# aurora-halo.net
KiCad netlist of a schematic drawn in EAGLE
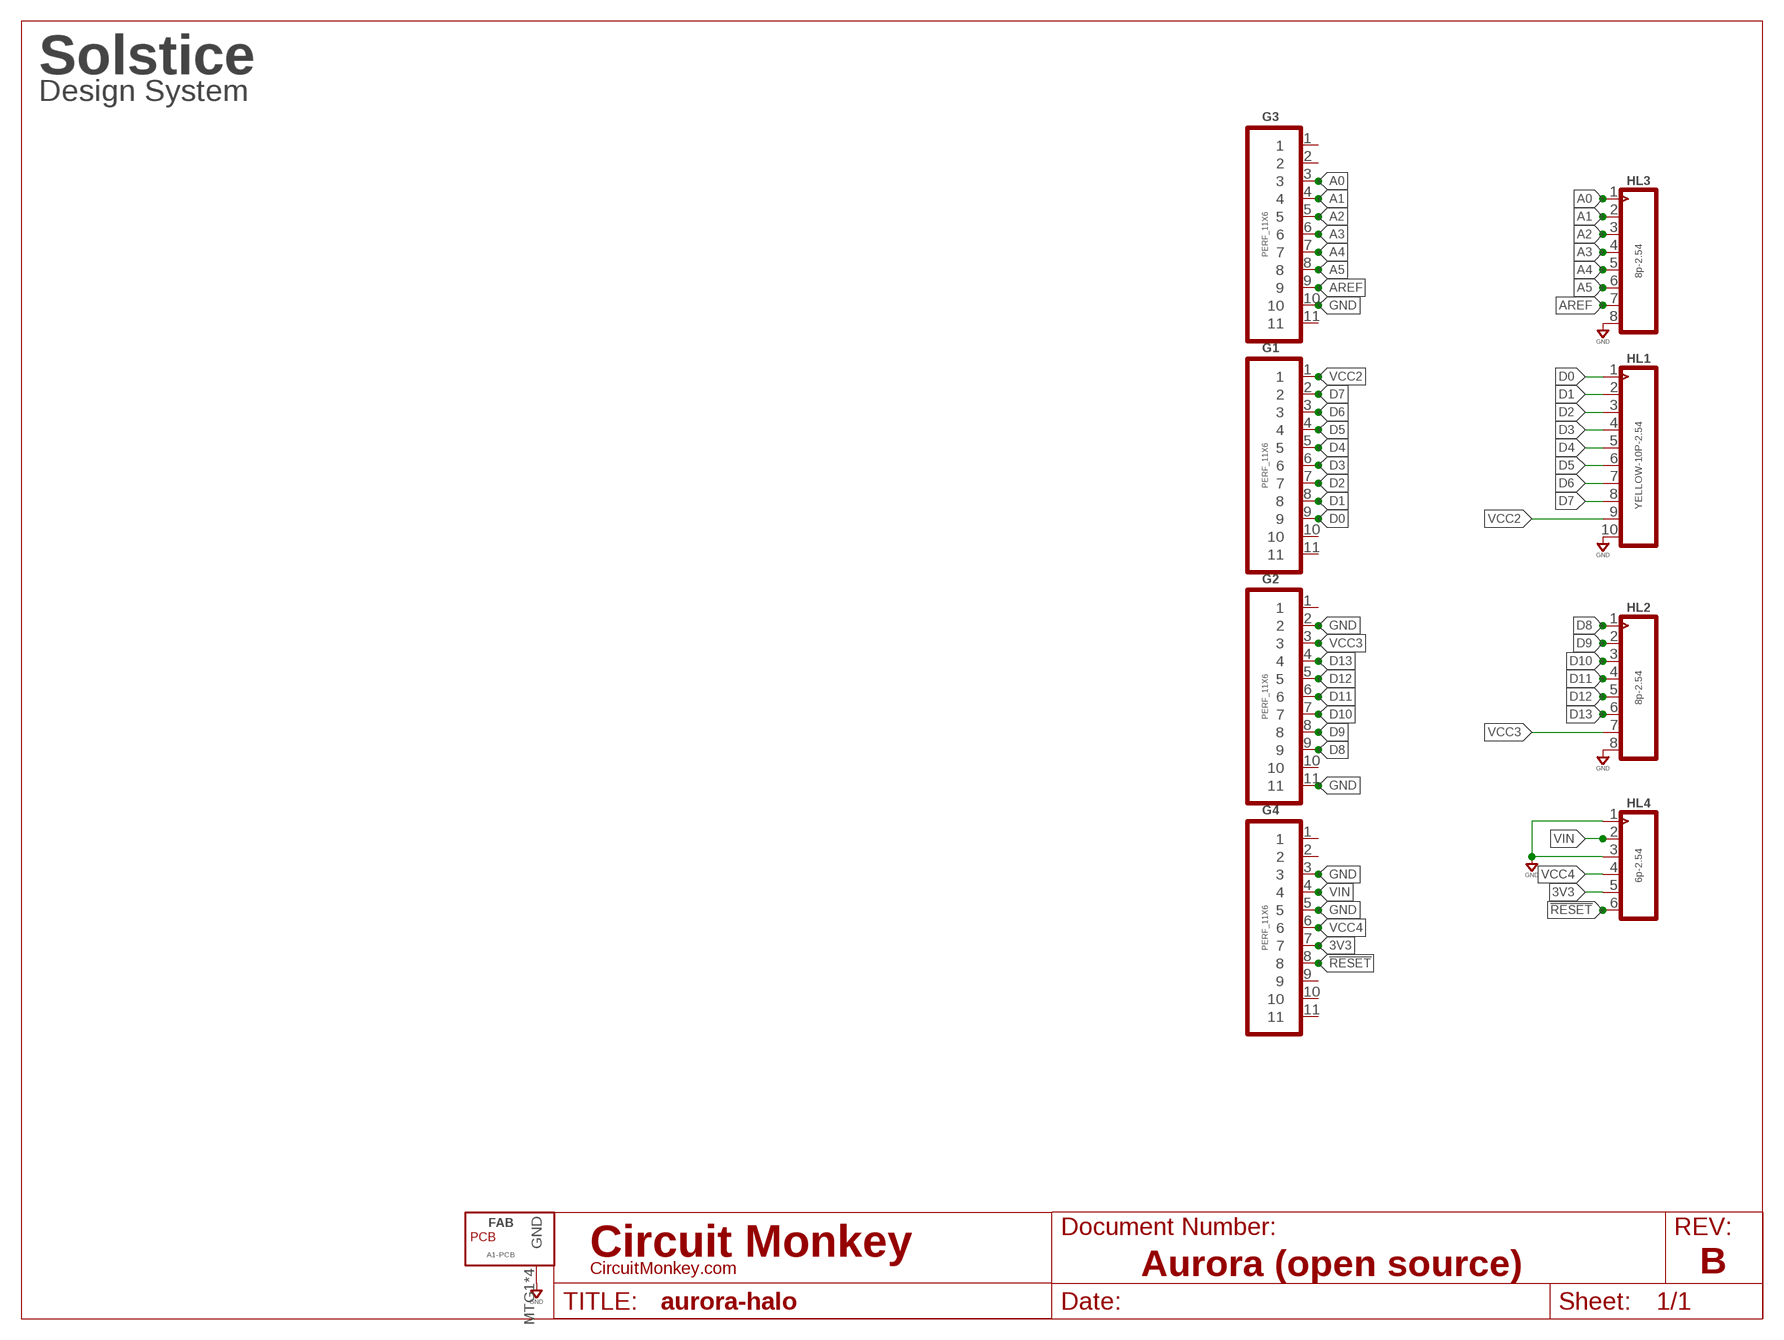
[diagram p0: schematic, sheet 1]

(export (version "E")
  (design (tool "Eeschema 10.0.6"))
  (components
    (comp (ref "FAB")
      (value "A1-PCB")
      (footprint "eagle-import:PCB-HALO-A1")
      (libsource (lib "eagle-import") (part "PCB-4-MTG-HALO-A1"))
    )
    (comp (ref "G1")
      (value "PERF_11X6")
      (footprint "eagle-import:PERF_6X11")
      (libsource (lib "eagle-import") (part "PERF_11X?6"))
    )
    (comp (ref "G2")
      (value "PERF_11X6")
      (footprint "eagle-import:PERF_6X11")
      (libsource (lib "eagle-import") (part "PERF_11X?6"))
    )
    (comp (ref "G3")
      (value "PERF_11X6")
      (footprint "eagle-import:PERF_6X11")
      (libsource (lib "eagle-import") (part "PERF_11X?6"))
    )
    (comp (ref "G4")
      (value "PERF_11X6")
      (footprint "eagle-import:PERF_6X11")
      (libsource (lib "eagle-import") (part "PERF_11X?6"))
    )
    (comp (ref "HL1")
      (value "YELLOW-10P-2.54")
      (footprint "eagle-import:H10-2.54")
      (fields (field (name "MPN") "F185-1110A1BSYC1"))
      (libsource (lib "eagle-import") (part "DIP-YELLOW-FEMALE-HEADER-VERT(10P-2.54)"))
    )
    (comp (ref "HL2")
      (value "8p-2.54")
      (footprint "eagle-import:H8-2.54")
      (fields (field (name "MPN") "F185-1108A1BSYC1"))
      (libsource (lib "eagle-import") (part "DIP-BLACK-FEMALE-HEADER-VERT(8P-2.54)"))
    )
    (comp (ref "HL3")
      (value "8p-2.54")
      (footprint "eagle-import:H8-2.54")
      (fields (field (name "MPN") "F185-1108A1BSYC1"))
      (libsource (lib "eagle-import") (part "DIP-BLACK-FEMALE-HEADER-VERT(8P-2.54)"))
    )
    (comp (ref "HL4")
      (value "6p-2.54")
      (footprint "eagle-import:H6-2.54")
      (fields (field (name "MPN") "F185-1106A1BSYC1"))
      (libsource (lib "eagle-import") (part "DIP-BLACK-FEMALE-HEADER-VERT(6P-2.54)"))
    )
  )
  (nets
    (net (code "1") (name "/~{RESET}") (class "Default")
      (node (ref "G4") (pin "8") (pinfunction "8_8") (pintype "bidirectional"))
      (node (ref "HL4") (pin "6") (pinfunction "6_6") (pintype "bidirectional"))
    )
    (net (code "2") (name "3V3") (class "Default")
      (node (ref "G4") (pin "7") (pinfunction "7_7") (pintype "bidirectional"))
      (node (ref "HL4") (pin "5") (pinfunction "5_5") (pintype "bidirectional"))
    )
    (net (code "3") (name "A0") (class "Default")
      (node (ref "G3") (pin "3") (pinfunction "3_3") (pintype "bidirectional"))
      (node (ref "HL3") (pin "1") (pinfunction "1_1") (pintype "bidirectional"))
    )
    (net (code "4") (name "A1") (class "Default")
      (node (ref "G3") (pin "4") (pinfunction "4_4") (pintype "bidirectional"))
      (node (ref "HL3") (pin "2") (pinfunction "2_2") (pintype "bidirectional"))
    )
    (net (code "5") (name "A2") (class "Default")
      (node (ref "G3") (pin "5") (pinfunction "5_5") (pintype "bidirectional"))
      (node (ref "HL3") (pin "3") (pinfunction "3_3") (pintype "bidirectional"))
    )
    (net (code "6") (name "A3") (class "Default")
      (node (ref "G3") (pin "6") (pinfunction "6_6") (pintype "bidirectional"))
      (node (ref "HL3") (pin "4") (pinfunction "4_4") (pintype "bidirectional"))
    )
    (net (code "7") (name "A4") (class "Default")
      (node (ref "G3") (pin "7") (pinfunction "7_7") (pintype "bidirectional"))
      (node (ref "HL3") (pin "5") (pinfunction "5_5") (pintype "bidirectional"))
    )
    (net (code "8") (name "A5") (class "Default")
      (node (ref "G3") (pin "8") (pinfunction "8_8") (pintype "bidirectional"))
      (node (ref "HL3") (pin "6") (pinfunction "6_6") (pintype "bidirectional"))
    )
    (net (code "9") (name "AREF") (class "Default")
      (node (ref "G3") (pin "9") (pinfunction "9_9") (pintype "bidirectional"))
      (node (ref "HL3") (pin "7") (pinfunction "7_7") (pintype "bidirectional"))
    )
    (net (code "10") (name "D0") (class "Default")
      (node (ref "G1") (pin "9") (pinfunction "9_9") (pintype "bidirectional"))
      (node (ref "HL1") (pin "1") (pinfunction "1_1") (pintype "bidirectional"))
    )
    (net (code "11") (name "D1") (class "Default")
      (node (ref "G1") (pin "8") (pinfunction "8_8") (pintype "bidirectional"))
      (node (ref "HL1") (pin "2") (pinfunction "2_2") (pintype "bidirectional"))
    )
    (net (code "12") (name "D2") (class "Default")
      (node (ref "G1") (pin "7") (pinfunction "7_7") (pintype "bidirectional"))
      (node (ref "HL1") (pin "3") (pinfunction "3_3") (pintype "bidirectional"))
    )
    (net (code "13") (name "D3") (class "Default")
      (node (ref "G1") (pin "6") (pinfunction "6_6") (pintype "bidirectional"))
      (node (ref "HL1") (pin "4") (pinfunction "4_4") (pintype "bidirectional"))
    )
    (net (code "14") (name "D4") (class "Default")
      (node (ref "G1") (pin "5") (pinfunction "5_5") (pintype "bidirectional"))
      (node (ref "HL1") (pin "5") (pinfunction "5_5") (pintype "bidirectional"))
    )
    (net (code "15") (name "D5") (class "Default")
      (node (ref "G1") (pin "4") (pinfunction "4_4") (pintype "bidirectional"))
      (node (ref "HL1") (pin "6") (pinfunction "6_6") (pintype "bidirectional"))
    )
    (net (code "16") (name "D6") (class "Default")
      (node (ref "G1") (pin "3") (pinfunction "3_3") (pintype "bidirectional"))
      (node (ref "HL1") (pin "7") (pinfunction "7_7") (pintype "bidirectional"))
    )
    (net (code "17") (name "D7") (class "Default")
      (node (ref "G1") (pin "2") (pinfunction "2_2") (pintype "bidirectional"))
      (node (ref "HL1") (pin "8") (pinfunction "8_8") (pintype "bidirectional"))
    )
    (net (code "18") (name "D8") (class "Default")
      (node (ref "G2") (pin "9") (pinfunction "9_9") (pintype "bidirectional"))
      (node (ref "HL2") (pin "1") (pinfunction "1_1") (pintype "bidirectional"))
    )
    (net (code "19") (name "D9") (class "Default")
      (node (ref "G2") (pin "8") (pinfunction "8_8") (pintype "bidirectional"))
      (node (ref "HL2") (pin "2") (pinfunction "2_2") (pintype "bidirectional"))
    )
    (net (code "20") (name "D10") (class "Default")
      (node (ref "G2") (pin "7") (pinfunction "7_7") (pintype "bidirectional"))
      (node (ref "HL2") (pin "3") (pinfunction "3_3") (pintype "bidirectional"))
    )
    (net (code "21") (name "D11") (class "Default")
      (node (ref "G2") (pin "6") (pinfunction "6_6") (pintype "bidirectional"))
      (node (ref "HL2") (pin "4") (pinfunction "4_4") (pintype "bidirectional"))
    )
    (net (code "22") (name "D12") (class "Default")
      (node (ref "G2") (pin "5") (pinfunction "5_5") (pintype "bidirectional"))
      (node (ref "HL2") (pin "5") (pinfunction "5_5") (pintype "bidirectional"))
    )
    (net (code "23") (name "D13") (class "Default")
      (node (ref "G2") (pin "4") (pinfunction "4_4") (pintype "bidirectional"))
      (node (ref "HL2") (pin "6") (pinfunction "6_6") (pintype "bidirectional"))
    )
    (net (code "24") (name "GND") (class "Default")
      (node (ref "FAB") (pin "MTG1") (pinfunction "GND_MTG1") (pintype "bidirectional"))
      (node (ref "FAB") (pin "MTG2") (pinfunction "GND_MTG2") (pintype "bidirectional"))
      (node (ref "FAB") (pin "MTG3") (pinfunction "GND_MTG3") (pintype "bidirectional"))
      (node (ref "FAB") (pin "MTG4") (pinfunction "GND_MTG4") (pintype "bidirectional"))
      (node (ref "G2") (pin "11") (pinfunction "11_11") (pintype "bidirectional"))
      (node (ref "G2") (pin "2") (pinfunction "2_2") (pintype "bidirectional"))
      (node (ref "G3") (pin "10") (pinfunction "10_10") (pintype "bidirectional"))
      (node (ref "G4") (pin "3") (pinfunction "3_3") (pintype "bidirectional"))
      (node (ref "G4") (pin "5") (pinfunction "5_5") (pintype "bidirectional"))
      (node (ref "HL1") (pin "10") (pinfunction "10_10") (pintype "bidirectional"))
      (node (ref "HL2") (pin "8") (pinfunction "8_8") (pintype "bidirectional"))
      (node (ref "HL3") (pin "8") (pinfunction "8_8") (pintype "bidirectional"))
      (node (ref "HL4") (pin "1") (pinfunction "1_1") (pintype "bidirectional"))
      (node (ref "HL4") (pin "3") (pinfunction "3_3") (pintype "bidirectional"))
    )
    (net (code "25") (name "VCC2") (class "Default")
      (node (ref "G1") (pin "1") (pinfunction "1_1") (pintype "bidirectional"))
      (node (ref "HL1") (pin "9") (pinfunction "9_9") (pintype "bidirectional"))
    )
    (net (code "26") (name "VCC3") (class "Default")
      (node (ref "G2") (pin "3") (pinfunction "3_3") (pintype "bidirectional"))
      (node (ref "HL2") (pin "7") (pinfunction "7_7") (pintype "bidirectional"))
    )
    (net (code "27") (name "VCC4") (class "Default")
      (node (ref "G4") (pin "6") (pinfunction "6_6") (pintype "bidirectional"))
      (node (ref "HL4") (pin "4") (pinfunction "4_4") (pintype "bidirectional"))
    )
    (net (code "28") (name "VIN") (class "Default")
      (node (ref "G4") (pin "4") (pinfunction "4_4") (pintype "bidirectional"))
      (node (ref "HL4") (pin "2") (pinfunction "2_2") (pintype "bidirectional"))
    )
    (net (code "29") (name "unconnected-(G1-Pad10)") (class "Default")
      (node (ref "G1") (pin "10") (pinfunction "10_10") (pintype "bidirectional"))
    )
    (net (code "30") (name "unconnected-(G1-Pad11)") (class "Default")
      (node (ref "G1") (pin "11") (pinfunction "11_11") (pintype "bidirectional"))
    )
    (net (code "31") (name "unconnected-(G2-Pad1)") (class "Default")
      (node (ref "G2") (pin "1") (pinfunction "1_1") (pintype "bidirectional"))
    )
    (net (code "32") (name "unconnected-(G2-Pad10)") (class "Default")
      (node (ref "G2") (pin "10") (pinfunction "10_10") (pintype "bidirectional"))
    )
    (net (code "33") (name "unconnected-(G3-Pad1)") (class "Default")
      (node (ref "G3") (pin "1") (pinfunction "1_1") (pintype "bidirectional"))
    )
    (net (code "34") (name "unconnected-(G3-Pad2)") (class "Default")
      (node (ref "G3") (pin "2") (pinfunction "2_2") (pintype "bidirectional"))
    )
    (net (code "35") (name "unconnected-(G3-Pad11)") (class "Default")
      (node (ref "G3") (pin "11") (pinfunction "11_11") (pintype "bidirectional"))
    )
    (net (code "36") (name "unconnected-(G4-Pad1)") (class "Default")
      (node (ref "G4") (pin "1") (pinfunction "1_1") (pintype "bidirectional"))
    )
    (net (code "37") (name "unconnected-(G4-Pad2)") (class "Default")
      (node (ref "G4") (pin "2") (pinfunction "2_2") (pintype "bidirectional"))
    )
    (net (code "38") (name "unconnected-(G4-Pad9)") (class "Default")
      (node (ref "G4") (pin "9") (pinfunction "9_9") (pintype "bidirectional"))
    )
    (net (code "39") (name "unconnected-(G4-Pad10)") (class "Default")
      (node (ref "G4") (pin "10") (pinfunction "10_10") (pintype "bidirectional"))
    )
    (net (code "40") (name "unconnected-(G4-Pad11)") (class "Default")
      (node (ref "G4") (pin "11") (pinfunction "11_11") (pintype "bidirectional"))
    )
  )
)
